# Headers.net
KiCad netlist of a schematic drawn in Altium Designer
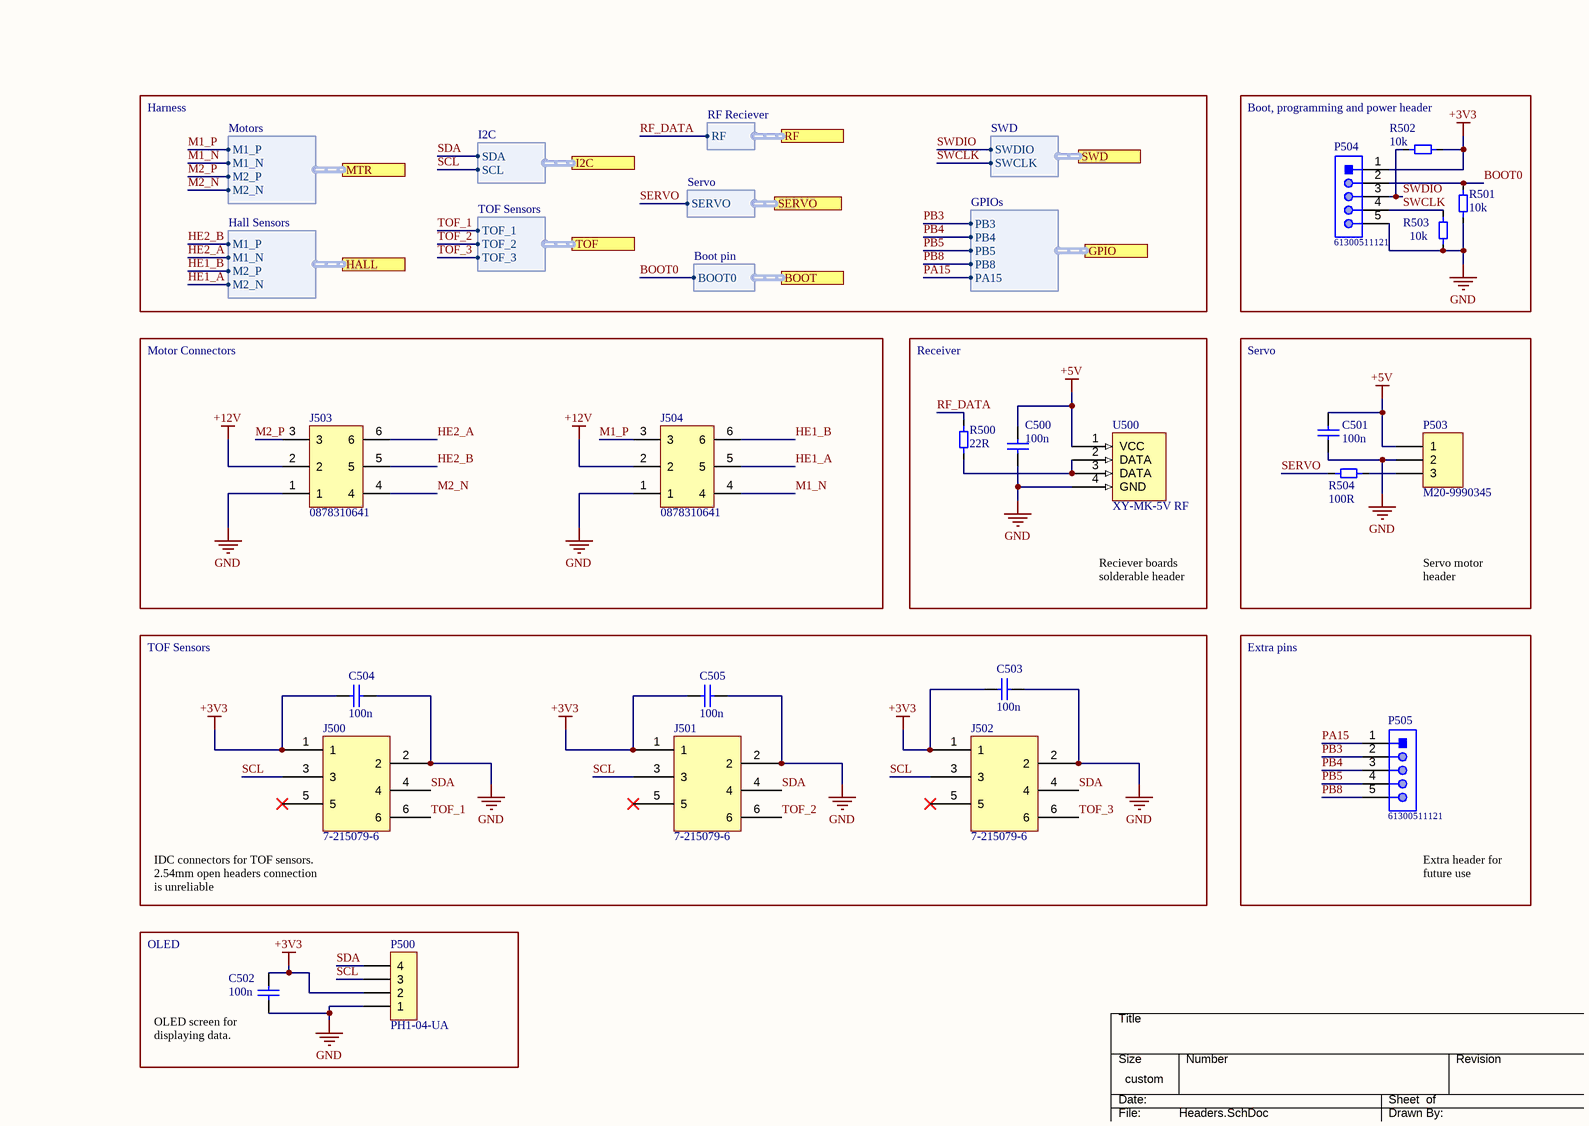
[diagram p0: Headers.SchDoc]

(export (version "E")
  (design (tool "Eeschema 10.0.6"))
  (components
    (comp (ref "C500")
      (value "100n")
      (footprint "MLCC_0603_M")
      (description "MLCC, 0603, 100n, 10%, 50V, X7R")
      (fields (field (name "VOLTAGE") "50V") (field (name "TOLERANCE") "10%"))
      (libsource (lib "Krakul Vault") (part "CAPACITOR_NONPOL_IEC"))
    )
    (comp (ref "C501")
      (value "100n")
      (footprint "MLCC_0603_M")
      (description "MLCC, 0603, 100n, 10%, 50V, X7R")
      (fields (field (name "VOLTAGE") "50V") (field (name "TOLERANCE") "10%"))
      (libsource (lib "Krakul Vault") (part "CAPACITOR_NONPOL_IEC"))
    )
    (comp (ref "C502")
      (value "100n")
      (footprint "MLCC_0603_M")
      (description "MLCC, 0603, 100n, 10%, 50V, X7R")
      (fields (field (name "VOLTAGE") "50V") (field (name "TOLERANCE") "10%"))
      (libsource (lib "Krakul Vault") (part "CAPACITOR_NONPOL_IEC"))
    )
    (comp (ref "C503")
      (value "100n")
      (footprint "MLCC_0603_M")
      (description "MLCC, 0603, 100n, 10%, 50V, X7R")
      (fields (field (name "VOLTAGE") "50V") (field (name "TOLERANCE") "10%"))
      (libsource (lib "Krakul Vault") (part "CAPACITOR_NONPOL_IEC"))
    )
    (comp (ref "C504")
      (value "100n")
      (footprint "MLCC_0603_M")
      (description "MLCC, 0603, 100n, 10%, 50V, X7R")
      (fields (field (name "VOLTAGE") "50V") (field (name "TOLERANCE") "10%"))
      (libsource (lib "Krakul Vault") (part "CAPACITOR_NONPOL_IEC"))
    )
    (comp (ref "C505")
      (value "100n")
      (footprint "MLCC_0603_M")
      (description "MLCC, 0603, 100n, 10%, 50V, X7R")
      (fields (field (name "VOLTAGE") "50V") (field (name "TOLERANCE") "10%"))
      (libsource (lib "Krakul Vault") (part "CAPACITOR_NONPOL_IEC"))
    )
    (comp (ref "J500")
      (value "7-215079-6")
      (footprint "7-215079-6-Footprint-1")
      (description "Conn FFC Connector F 6 POS 1.27mm Solder ST Thru-Hole Automotive Box/Carton")
      (fields (field (name "MANUFACTURER") "TE Connectivity"))
      (libsource (lib "Krakul Vault") (part "7-215079-6"))
    )
    (comp (ref "J501")
      (value "7-215079-6")
      (footprint "7-215079-6-Footprint-1")
      (description "Conn FFC Connector F 6 POS 1.27mm Solder ST Thru-Hole Automotive Box/Carton")
      (fields (field (name "MANUFACTURER") "TE Connectivity"))
      (libsource (lib "Krakul Vault") (part "7-215079-6"))
    )
    (comp (ref "J502")
      (value "7-215079-6")
      (footprint "7-215079-6-Footprint-1")
      (description "Conn FFC Connector F 6 POS 1.27mm Solder ST Thru-Hole Automotive Box/Carton")
      (fields (field (name "MANUFACTURER") "TE Connectivity"))
      (libsource (lib "Krakul Vault") (part "7-215079-6"))
    )
    (comp (ref "J503")
      (value "0878310641")
      (footprint "0878310641")
      (description "Conn Shrouded Header (2 Sides) HDR 6 POS 2mm Solder ST Top Entry Thru-Hole Milli-Grid Tube")
      (fields (field (name "MANUFACTURER") "Molex"))
      (libsource (lib "Krakul Vault") (part "0878310641"))
    )
    (comp (ref "J504")
      (value "0878310641")
      (footprint "0878310641")
      (description "Conn Shrouded Header (2 Sides) HDR 6 POS 2mm Solder ST Top Entry Thru-Hole Milli-Grid Tube")
      (fields (field (name "MANUFACTURER") "Molex"))
      (libsource (lib "Krakul Vault") (part "0878310641"))
    )
    (comp (ref "P500")
      (value "PH1-04-UA")
      (footprint "4Pos Pin Header Vertical")
      (description "4 POS 2.54mm Vertical THT Header")
      (fields (field (name "MANUFACTURER") "Adam Tech"))
      (libsource (lib "Krakul Vault") (part "4POS GENERIC"))
    )
    (comp (ref "P503")
      (value "M20-9990345")
      (footprint "3Pos Pin Header")
      (description "Connector Header Through Hole 3 position 0.100\" (2.54mm)")
      (fields (field (name "MANUFACTURER") "Harwin Inc."))
      (libsource (lib "Krakul Vault") (part "3 pin header"))
    )
    (comp (ref "P504")
      (value "61300511121")
      (footprint "61300511121")
      (description "Conn Unshrouded Header HDR 5 POS 2.54mm Solder ST Top Entry Thru-Hole Bag")
      (fields (field (name "MANUFACTURER") "Wurth"))
      (libsource (lib "Krakul Vault") (part "WE-CN-1P-M-R5"))
    )
    (comp (ref "P505")
      (value "61300511121")
      (footprint "61300511121")
      (description "Conn Unshrouded Header HDR 5 POS 2.54mm Solder ST Top Entry Thru-Hole Bag")
      (fields (field (name "MANUFACTURER") "Wurth"))
      (libsource (lib "") (part "WE-CN-1P-M-R5_1"))
    )
    (comp (ref "R500")
      (value "22R")
      (footprint "Resistor_0603_M")
      (description "Resistor, 0603, 22R, 1%, 1/10W")
      (fields (field (name "TOLERANCE") "1%") (field (name "MANUFACTURER") "Any"))
      (libsource (lib "Krakul Vault") (part "RESISTOR_GENERIC_IEC"))
    )
    (comp (ref "R501")
      (value "10k")
      (footprint "Resistor_0603_M")
      (description "Resistor, 0603, 10k, ≤5%, ≥1/16W")
      (fields (field (name "MANUFACTURER") "Any"))
      (libsource (lib "Krakul Vault") (part "RESISTOR_GENERIC_IEC"))
    )
    (comp (ref "R502")
      (value "10k")
      (footprint "Resistor_0603_M")
      (description "Resistor, 0603, 10k, 1%, 1/10W")
      (fields (field (name "MANUFACTURER") "Any") (field (name "TOLERANCE") "1%"))
      (libsource (lib "Krakul Vault") (part "RESISTOR_GENERIC_IEC"))
    )
    (comp (ref "R503")
      (value "10k")
      (footprint "Resistor_0603_M")
      (description "Resistor, 0603, 10k, 1%, 1/10W")
      (fields (field (name "MANUFACTURER") "Any") (field (name "TOLERANCE") "1%"))
      (libsource (lib "Krakul Vault") (part "RESISTOR_GENERIC_IEC"))
    )
    (comp (ref "R504")
      (value "100R")
      (footprint "Resistor_0603_M")
      (description "Resistor, 0603, 100R, 1%, 1/10W")
      (fields (field (name "POWER") "100mW") (field (name "MANUFACTURER") "Any"))
      (libsource (lib "Krakul Vault") (part "RESISTOR_GENERIC_IEC"))
    )
    (comp (ref "U500")
      (value "XY-MK-5V RF")
      (footprint "2.54mm 4 POS XY-MK-5V RF")
      (description "433MHz reciever module, 5V tolerant")
      (fields (field (name "MANUFACTURER") "Unknown"))
      (libsource (lib "Krakul Vault") (part "XY-MK-5V RF-Symbol-1"))
    )
  )
  (nets
    (net (code "13") (name "+3V3") (class "Default")
      (node (ref "C502") (pin "1") (pinfunction "1_1") (pintype "passive"))
      (node (ref "C503") (pin "1") (pinfunction "1_1") (pintype "passive"))
      (node (ref "C504") (pin "1") (pinfunction "1_1") (pintype "passive"))
      (node (ref "C505") (pin "1") (pinfunction "1_1") (pintype "passive"))
      (node (ref "J500") (pin "1") (pinfunction "1_1") (pintype "passive"))
      (node (ref "J501") (pin "1") (pinfunction "1_1") (pintype "passive"))
      (node (ref "J502") (pin "1") (pinfunction "1_1") (pintype "passive"))
      (node (ref "P500") (pin "2") (pinfunction "2_2") (pintype "passive"))
      (node (ref "P504") (pin "1") (pinfunction "1_1") (pintype "passive"))
      (node (ref "R502") (pin "1") (pinfunction "1_1") (pintype "passive"))
    )
    (net (code "14") (name "+5V") (class "Default")
      (node (ref "C500") (pin "1") (pinfunction "1_1") (pintype "passive"))
      (node (ref "C501") (pin "1") (pinfunction "1_1") (pintype "passive"))
      (node (ref "P503") (pin "1") (pinfunction "1_1") (pintype "passive"))
      (node (ref "U500") (pin "1") (pinfunction "VCC_1") (pintype "input"))
    )
    (net (code "15") (name "+12V") (class "Default")
      (node (ref "J503") (pin "2") (pinfunction "2_2") (pintype "passive"))
      (node (ref "J504") (pin "2") (pinfunction "2_2") (pintype "passive"))
    )
    (net (code "16") (name "/BOOT0") (class "Default")
      (node (ref "P504") (pin "2") (pinfunction "2_2") (pintype "passive"))
      (node (ref "R501") (pin "2") (pinfunction "2_2") (pintype "passive"))
    )
    (net (code "17") (name "/HE1_A") (class "Default")
      (node (ref "J504") (pin "5") (pinfunction "5_5") (pintype "passive"))
    )
    (net (code "18") (name "/HE1_B") (class "Default")
      (node (ref "J504") (pin "6") (pinfunction "6_6") (pintype "passive"))
    )
    (net (code "19") (name "/HE2_A") (class "Default")
      (node (ref "J503") (pin "6") (pinfunction "6_6") (pintype "passive"))
    )
    (net (code "20") (name "/HE2_B") (class "Default")
      (node (ref "J503") (pin "5") (pinfunction "5_5") (pintype "passive"))
    )
    (net (code "21") (name "/M1_N") (class "Default")
      (node (ref "J504") (pin "4") (pinfunction "4_4") (pintype "passive"))
    )
    (net (code "22") (name "/M1_P") (class "Default")
      (node (ref "J504") (pin "3") (pinfunction "3_3") (pintype "passive"))
    )
    (net (code "23") (name "/M2_N") (class "Default")
      (node (ref "J503") (pin "4") (pinfunction "4_4") (pintype "passive"))
    )
    (net (code "24") (name "/M2_P") (class "Default")
      (node (ref "J503") (pin "3") (pinfunction "3_3") (pintype "passive"))
    )
    (net (code "25") (name "/PA15") (class "Default")
      (node (ref "P505") (pin "1") (pinfunction "1_1") (pintype "passive"))
    )
    (net (code "26") (name "/PB3") (class "Default")
      (node (ref "P505") (pin "2") (pinfunction "2_2") (pintype "passive"))
    )
    (net (code "27") (name "/PB4") (class "Default")
      (node (ref "P505") (pin "3") (pinfunction "3_3") (pintype "passive"))
    )
    (net (code "28") (name "/PB5") (class "Default")
      (node (ref "P505") (pin "4") (pinfunction "4_4") (pintype "passive"))
    )
    (net (code "29") (name "/PB8") (class "Default")
      (node (ref "P505") (pin "5") (pinfunction "5_5") (pintype "passive"))
    )
    (net (code "30") (name "/RF_DATA") (class "Default")
      (node (ref "R500") (pin "1") (pinfunction "1_1") (pintype "passive"))
    )
    (net (code "31") (name "/SCL") (class "Default")
      (node (ref "J500") (pin "3") (pinfunction "3_3") (pintype "passive"))
      (node (ref "J501") (pin "3") (pinfunction "3_3") (pintype "passive"))
      (node (ref "J502") (pin "3") (pinfunction "3_3") (pintype "passive"))
      (node (ref "P500") (pin "3") (pinfunction "3_3") (pintype "passive"))
    )
    (net (code "32") (name "/SDA") (class "Default")
      (node (ref "J500") (pin "4") (pinfunction "4_4") (pintype "passive"))
      (node (ref "J501") (pin "4") (pinfunction "4_4") (pintype "passive"))
      (node (ref "J502") (pin "4") (pinfunction "4_4") (pintype "passive"))
      (node (ref "P500") (pin "4") (pinfunction "4_4") (pintype "passive"))
    )
    (net (code "33") (name "/SERVO") (class "Default")
      (node (ref "R504") (pin "2") (pinfunction "2_2") (pintype "passive"))
    )
    (net (code "34") (name "/SWCLK") (class "Default")
      (node (ref "P504") (pin "4") (pinfunction "4_4") (pintype "passive"))
      (node (ref "R503") (pin "2") (pinfunction "2_2") (pintype "passive"))
    )
    (net (code "35") (name "/SWDIO") (class "Default")
      (node (ref "P504") (pin "3") (pinfunction "3_3") (pintype "passive"))
      (node (ref "R502") (pin "2") (pinfunction "2_2") (pintype "passive"))
    )
    (net (code "36") (name "/TOF_1") (class "Default")
      (node (ref "J500") (pin "6") (pinfunction "6_6") (pintype "passive"))
    )
    (net (code "37") (name "/TOF_2") (class "Default")
      (node (ref "J501") (pin "6") (pinfunction "6_6") (pintype "passive"))
    )
    (net (code "38") (name "/TOF_3") (class "Default")
      (node (ref "J502") (pin "6") (pinfunction "6_6") (pintype "passive"))
    )
    (net (code "48") (name "GND") (class "Default")
      (node (ref "C500") (pin "2") (pinfunction "2_2") (pintype "passive"))
      (node (ref "C501") (pin "2") (pinfunction "2_2") (pintype "passive"))
      (node (ref "C502") (pin "2") (pinfunction "2_2") (pintype "passive"))
      (node (ref "C503") (pin "2") (pinfunction "2_2") (pintype "passive"))
      (node (ref "C504") (pin "2") (pinfunction "2_2") (pintype "passive"))
      (node (ref "C505") (pin "2") (pinfunction "2_2") (pintype "passive"))
      (node (ref "J500") (pin "2") (pinfunction "2_2") (pintype "passive"))
      (node (ref "J501") (pin "2") (pinfunction "2_2") (pintype "passive"))
      (node (ref "J502") (pin "2") (pinfunction "2_2") (pintype "passive"))
      (node (ref "J503") (pin "1") (pinfunction "1_1") (pintype "passive"))
      (node (ref "J504") (pin "1") (pinfunction "1_1") (pintype "passive"))
      (node (ref "P500") (pin "1") (pinfunction "1_1") (pintype "passive"))
      (node (ref "P503") (pin "2") (pinfunction "2_2") (pintype "passive"))
      (node (ref "P504") (pin "5") (pinfunction "5_5") (pintype "passive"))
      (node (ref "R501") (pin "1") (pinfunction "1_1") (pintype "passive"))
      (node (ref "R503") (pin "1") (pinfunction "1_1") (pintype "passive"))
      (node (ref "U500") (pin "4") (pinfunction "GND_4") (pintype "input"))
    )
    (net (code "49") (name "Net-(P503-Pad3)") (class "Default")
      (node (ref "P503") (pin "3") (pinfunction "3_3") (pintype "passive"))
      (node (ref "R504") (pin "1") (pinfunction "1_1") (pintype "passive"))
    )
    (net (code "50") (name "Net-(R500-Pad2)") (class "Default")
      (node (ref "R500") (pin "2") (pinfunction "2_2") (pintype "passive"))
      (node (ref "U500") (pin "2") (pinfunction "DATA_2") (pintype "input"))
      (node (ref "U500") (pin "3") (pinfunction "DATA_3") (pintype "input"))
    )
    (net (code "51") (name "unconnected-(J500-Pad5)") (class "Default")
      (node (ref "J500") (pin "5") (pinfunction "5_5") (pintype "passive+no_connect"))
    )
    (net (code "52") (name "unconnected-(J501-Pad5)") (class "Default")
      (node (ref "J501") (pin "5") (pinfunction "5_5") (pintype "passive+no_connect"))
    )
    (net (code "53") (name "unconnected-(J502-Pad5)") (class "Default")
      (node (ref "J502") (pin "5") (pinfunction "5_5") (pintype "passive+no_connect"))
    )
  )
)
